# sch_ma_carte_alim_v1_1.net
KiCad netlist of a schematic drawn in EAGLE
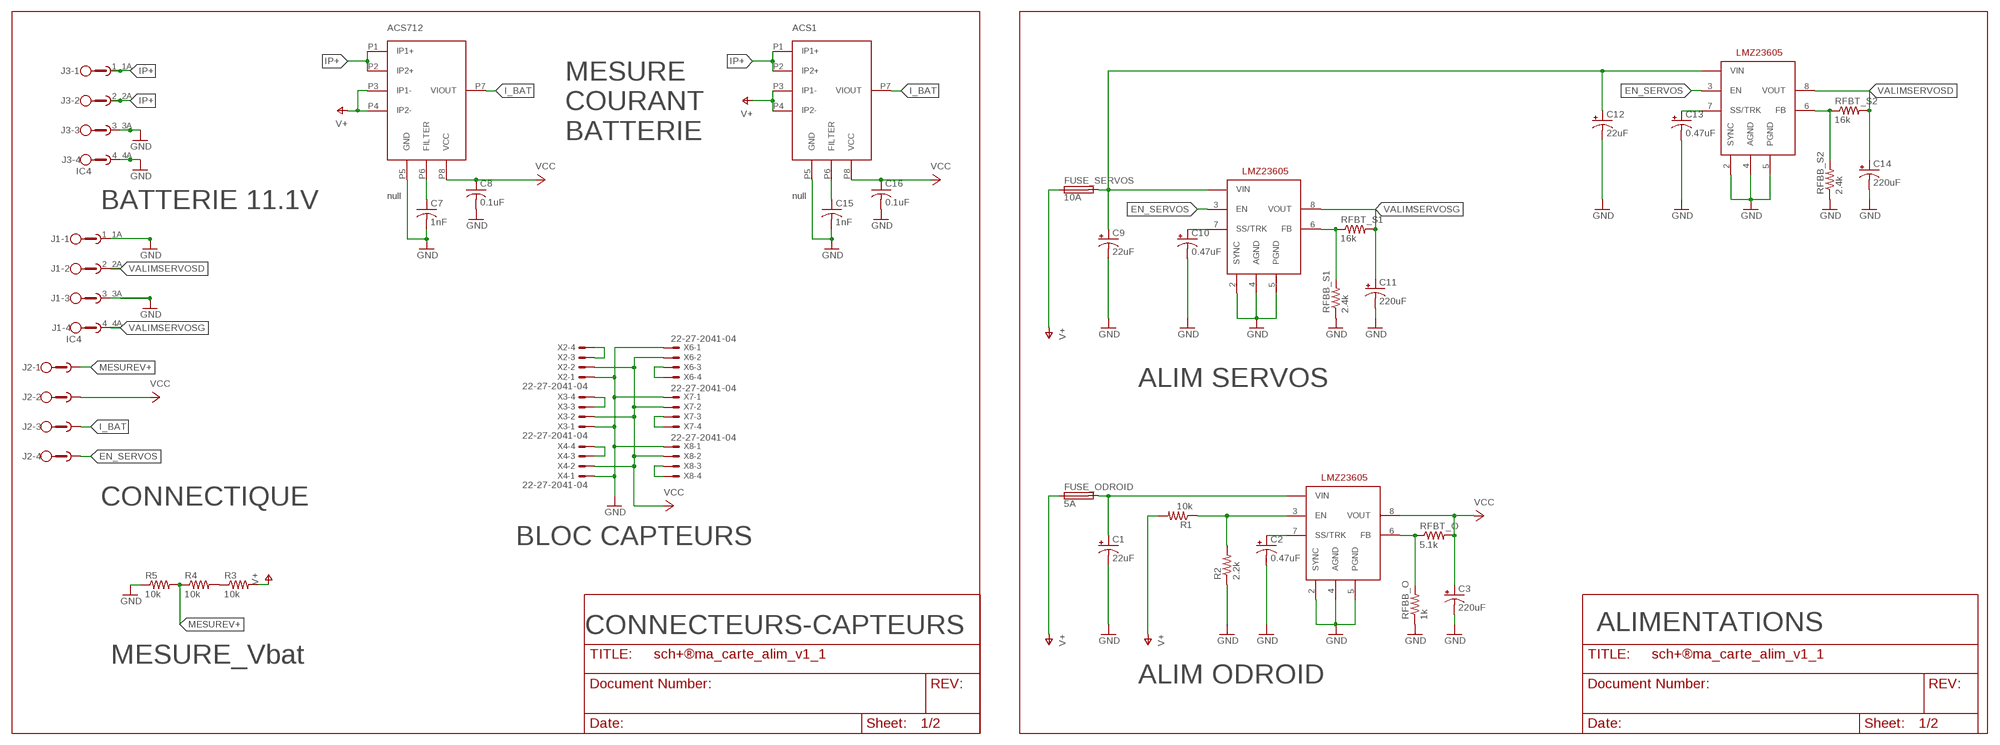
[diagram p0: schematic, sheet 1]

(export (version "E")
  (design (tool "Eeschema 10.0.6"))
  (components
    (comp (ref "ACS1")
      (value "null")
      (footprint "eagle-import:ACS712")
      (libsource (lib "eagle-import") (part "ACS712"))
    )
    (comp (ref "ACS712")
      (value "null")
      (footprint "eagle-import:ACS712")
      (libsource (lib "eagle-import") (part "ACS712"))
    )
    (comp (ref "ALIM_ODROID")
      (value "LMZ23605")
      (footprint "eagle-import:LMZ23605")
      (libsource (lib "eagle-import") (part "LMZ23605"))
    )
    (comp (ref "ALIM_SERVOS1")
      (value "LMZ23605")
      (footprint "eagle-import:LMZ23605")
      (libsource (lib "eagle-import") (part "LMZ23605"))
    )
    (comp (ref "ALIM_SERVOS2")
      (value "LMZ23605")
      (footprint "eagle-import:LMZ23605")
      (libsource (lib "eagle-import") (part "LMZ23605"))
    )
    (comp (ref "C1")
      (value "22uF")
      (footprint "eagle-import:E2,5-6")
      (libsource (lib "eagle-import") (part "CPOL-USE2.5-6"))
    )
    (comp (ref "C2")
      (value "0.47uF")
      (footprint "eagle-import:E2-5")
      (libsource (lib "eagle-import") (part "CPOL-USE2-5"))
    )
    (comp (ref "C3")
      (value "220uF")
      (footprint "eagle-import:E3,5-8")
      (libsource (lib "eagle-import") (part "CPOL-USE3.5-8"))
    )
    (comp (ref "C7")
      (value "1nF")
      (footprint "eagle-import:C0805")
      (libsource (lib "eagle-import") (part "C-USC0805"))
    )
    (comp (ref "C8")
      (value "0.1uF")
      (footprint "eagle-import:C0805")
      (libsource (lib "eagle-import") (part "C-USC0805"))
    )
    (comp (ref "C9")
      (value "22uF")
      (footprint "eagle-import:E2,5-6")
      (libsource (lib "eagle-import") (part "CPOL-USE2.5-6"))
    )
    (comp (ref "C10")
      (value "0.47uF")
      (footprint "eagle-import:E2-5")
      (libsource (lib "eagle-import") (part "CPOL-USE2-5"))
    )
    (comp (ref "C11")
      (value "220uF")
      (footprint "eagle-import:E3,5-8")
      (libsource (lib "eagle-import") (part "CPOL-USE3.5-8"))
    )
    (comp (ref "C12")
      (value "22uF")
      (footprint "eagle-import:E2,5-6")
      (libsource (lib "eagle-import") (part "CPOL-USE2.5-6"))
    )
    (comp (ref "C13")
      (value "0.47uF")
      (footprint "eagle-import:E2-5")
      (libsource (lib "eagle-import") (part "CPOL-USE2-5"))
    )
    (comp (ref "C14")
      (value "220uF")
      (footprint "eagle-import:E3,5-8")
      (libsource (lib "eagle-import") (part "CPOL-USE3.5-8"))
    )
    (comp (ref "C15")
      (value "1nF")
      (footprint "eagle-import:C0805")
      (libsource (lib "eagle-import") (part "C-USC0805"))
    )
    (comp (ref "C16")
      (value "0.1uF")
      (footprint "eagle-import:C0805")
      (libsource (lib "eagle-import") (part "C-USC0805"))
    )
    (comp (ref "FUSE_ODROID")
      (value "5A")
      (footprint "eagle-import:SH22,5")
      (fields (field (name "MF") "SCHURTER") (field (name "MPN") "0031.8201"))
      (libsource (lib "eagle-import") (part "SH22,5"))
    )
    (comp (ref "FUSE_SERVOS")
      (value "10A")
      (footprint "eagle-import:SH22,5")
      (fields (field (name "MF") "SCHURTER") (field (name "MPN") "0031.8201"))
      (libsource (lib "eagle-import") (part "SH22,5"))
    )
    (comp (ref "J1")
      (value "IC4")
      (footprint "eagle-import:IC4")
      (libsource (lib "eagle-import") (part "IC4"))
    )
    (comp (ref "J2")
      (value "MC1.5/4-G-3.81")
      (footprint "eagle-import:MC1.5_4-G-3.81")
      (libsource (lib "eagle-import") (part "MC1.5/4-G-3.81"))
    )
    (comp (ref "J3")
      (value "IC4")
      (footprint "eagle-import:IC4")
      (libsource (lib "eagle-import") (part "IC4"))
    )
    (comp (ref "R1")
      (value "10k")
      (footprint "eagle-import:R0805")
      (libsource (lib "eagle-import") (part "R-US_R0805"))
    )
    (comp (ref "R2")
      (value "2.2k")
      (footprint "eagle-import:R0805")
      (libsource (lib "eagle-import") (part "R-US_R0805"))
    )
    (comp (ref "R3")
      (value "10k")
      (footprint "eagle-import:M0805")
      (libsource (lib "eagle-import") (part "R-US_M0805"))
    )
    (comp (ref "R4")
      (value "10k")
      (footprint "eagle-import:M0805")
      (libsource (lib "eagle-import") (part "R-US_M0805"))
    )
    (comp (ref "R5")
      (value "10k")
      (footprint "eagle-import:M0805")
      (libsource (lib "eagle-import") (part "R-US_M0805"))
    )
    (comp (ref "RFBB_O")
      (value "1k")
      (footprint "eagle-import:R0805")
      (libsource (lib "eagle-import") (part "R-US_R0805"))
    )
    (comp (ref "RFBB_S1")
      (value "2.4k")
      (footprint "eagle-import:R0805")
      (libsource (lib "eagle-import") (part "R-US_R0805"))
    )
    (comp (ref "RFBB_S2")
      (value "2.4k")
      (footprint "eagle-import:R0805")
      (libsource (lib "eagle-import") (part "R-US_R0805"))
    )
    (comp (ref "RFBT_O")
      (value "5.1k")
      (footprint "eagle-import:R0805")
      (libsource (lib "eagle-import") (part "R-US_R0805"))
    )
    (comp (ref "RFBT_S1")
      (value "16k")
      (footprint "eagle-import:R0805")
      (libsource (lib "eagle-import") (part "R-US_R0805"))
    )
    (comp (ref "RFBT_S2")
      (value "16k")
      (footprint "eagle-import:R0805")
      (libsource (lib "eagle-import") (part "R-US_R0805"))
    )
    (comp (ref "X2")
      (value "22-27-2041-04")
      (footprint "eagle-import:6410-04")
      (libsource (lib "eagle-import") (part "22-?-0427-2041"))
    )
    (comp (ref "X3")
      (value "22-27-2041-04")
      (footprint "eagle-import:6410-04")
      (libsource (lib "eagle-import") (part "22-?-0427-2041"))
    )
    (comp (ref "X4")
      (value "22-27-2041-04")
      (footprint "eagle-import:6410-04")
      (libsource (lib "eagle-import") (part "22-?-0427-2041"))
    )
    (comp (ref "X6")
      (value "22-27-2041-04")
      (footprint "eagle-import:6410-04")
      (libsource (lib "eagle-import") (part "22-?-0427-2041"))
    )
    (comp (ref "X7")
      (value "22-27-2041-04")
      (footprint "eagle-import:6410-04")
      (libsource (lib "eagle-import") (part "22-?-0427-2041"))
    )
    (comp (ref "X8")
      (value "22-27-2041-04")
      (footprint "eagle-import:6410-04")
      (libsource (lib "eagle-import") (part "22-?-0427-2041"))
    )
  )
  (nets
    (net (code "1") (name "EN_SERVOS") (class "Default")
      (node (ref "ALIM_SERVOS1") (pin "3") (pinfunction "EN_3") (pintype "bidirectional"))
      (node (ref "ALIM_SERVOS2") (pin "3") (pinfunction "EN_3") (pintype "bidirectional"))
      (node (ref "J2") (pin "4") (pinfunction "1_4") (pintype "passive"))
    )
    (net (code "2") (name "GND") (class "Default")
      (node (ref "ACS1") (pin "P5") (pinfunction "GND_P5") (pintype "power_in"))
      (node (ref "ACS712") (pin "P5") (pinfunction "GND_P5") (pintype "power_in"))
      (node (ref "ALIM_ODROID") (pin "2") (pinfunction "SYNC_2") (pintype "bidirectional"))
      (node (ref "ALIM_ODROID") (pin "4") (pinfunction "AGND_4") (pintype "bidirectional"))
      (node (ref "ALIM_ODROID") (pin "5") (pinfunction "PGND_5") (pintype "bidirectional"))
      (node (ref "ALIM_SERVOS1") (pin "2") (pinfunction "SYNC_2") (pintype "bidirectional"))
      (node (ref "ALIM_SERVOS1") (pin "4") (pinfunction "AGND_4") (pintype "bidirectional"))
      (node (ref "ALIM_SERVOS1") (pin "5") (pinfunction "PGND_5") (pintype "bidirectional"))
      (node (ref "ALIM_SERVOS2") (pin "2") (pinfunction "SYNC_2") (pintype "bidirectional"))
      (node (ref "ALIM_SERVOS2") (pin "4") (pinfunction "AGND_4") (pintype "bidirectional"))
      (node (ref "ALIM_SERVOS2") (pin "5") (pinfunction "PGND_5") (pintype "bidirectional"))
      (node (ref "C1") (pin "-") (pinfunction "-_-") (pintype "passive"))
      (node (ref "C10") (pin "-") (pinfunction "-_-") (pintype "passive"))
      (node (ref "C11") (pin "-") (pinfunction "-_-") (pintype "passive"))
      (node (ref "C12") (pin "-") (pinfunction "-_-") (pintype "passive"))
      (node (ref "C13") (pin "-") (pinfunction "-_-") (pintype "passive"))
      (node (ref "C14") (pin "-") (pinfunction "-_-") (pintype "passive"))
      (node (ref "C15") (pin "2") (pinfunction "2_2") (pintype "passive"))
      (node (ref "C16") (pin "2") (pinfunction "2_2") (pintype "passive"))
      (node (ref "C2") (pin "-") (pinfunction "-_-") (pintype "passive"))
      (node (ref "C3") (pin "-") (pinfunction "-_-") (pintype "passive"))
      (node (ref "C7") (pin "2") (pinfunction "2_2") (pintype "passive"))
      (node (ref "C8") (pin "2") (pinfunction "2_2") (pintype "passive"))
      (node (ref "C9") (pin "-") (pinfunction "-_-") (pintype "passive"))
      (node (ref "J1") (pin "1") (pinfunction "1_1") (pintype "passive"))
      (node (ref "J1") (pin "1A") (pinfunction "2_1A") (pintype "passive"))
      (node (ref "J1") (pin "3") (pinfunction "1_3") (pintype "passive"))
      (node (ref "J1") (pin "3A") (pinfunction "2_3A") (pintype "passive"))
      (node (ref "J3") (pin "3") (pinfunction "1_3") (pintype "passive"))
      (node (ref "J3") (pin "3A") (pinfunction "2_3A") (pintype "passive"))
      (node (ref "J3") (pin "4") (pinfunction "1_4") (pintype "passive"))
      (node (ref "J3") (pin "4A") (pinfunction "2_4A") (pintype "passive"))
      (node (ref "R2") (pin "1") (pinfunction "1_1") (pintype "passive"))
      (node (ref "R5") (pin "1") (pinfunction "1_1") (pintype "passive"))
      (node (ref "RFBB_O") (pin "1") (pinfunction "1_1") (pintype "passive"))
      (node (ref "RFBB_S1") (pin "1") (pinfunction "1_1") (pintype "passive"))
      (node (ref "RFBB_S2") (pin "1") (pinfunction "1_1") (pintype "passive"))
      (node (ref "X2") (pin "1") (pinfunction "S_1") (pintype "passive"))
      (node (ref "X3") (pin "1") (pinfunction "S_1") (pintype "passive"))
      (node (ref "X4") (pin "1") (pinfunction "S_1") (pintype "passive"))
      (node (ref "X6") (pin "1") (pinfunction "S_1") (pintype "passive"))
      (node (ref "X7") (pin "1") (pinfunction "S_1") (pintype "passive"))
      (node (ref "X8") (pin "1") (pinfunction "S_1") (pintype "passive"))
    )
    (net (code "3") (name "IP+") (class "Default")
      (node (ref "ACS1") (pin "P1") (pinfunction "IP1+_P1") (pintype "input"))
      (node (ref "ACS1") (pin "P2") (pinfunction "IP2+_P2") (pintype "input"))
      (node (ref "ACS712") (pin "P1") (pinfunction "IP1+_P1") (pintype "input"))
      (node (ref "ACS712") (pin "P2") (pinfunction "IP2+_P2") (pintype "input"))
      (node (ref "J3") (pin "1") (pinfunction "1_1") (pintype "passive"))
      (node (ref "J3") (pin "1A") (pinfunction "2_1A") (pintype "passive"))
      (node (ref "J3") (pin "2") (pinfunction "1_2") (pintype "passive"))
      (node (ref "J3") (pin "2A") (pinfunction "2_2A") (pintype "passive"))
    )
    (net (code "4") (name "I_BAT") (class "Default")
      (node (ref "ACS1") (pin "P7") (pinfunction "VIOUT_P7") (pintype "output"))
      (node (ref "ACS712") (pin "P7") (pinfunction "VIOUT_P7") (pintype "output"))
      (node (ref "J2") (pin "3") (pinfunction "1_3") (pintype "passive"))
    )
    (net (code "5") (name "MESUREV+") (class "Default")
      (node (ref "J2") (pin "1") (pinfunction "1_1") (pintype "passive"))
      (node (ref "R4") (pin "1") (pinfunction "1_1") (pintype "passive"))
      (node (ref "R5") (pin "2") (pinfunction "2_2") (pintype "passive"))
    )
    (net (code "6") (name "Net-(ACS1-FILTER)") (class "Default")
      (node (ref "ACS1") (pin "P6") (pinfunction "FILTER_P6") (pintype "bidirectional"))
      (node (ref "C15") (pin "1") (pinfunction "1_1") (pintype "passive"))
    )
    (net (code "7") (name "Net-(ACS712-FILTER)") (class "Default")
      (node (ref "ACS712") (pin "P6") (pinfunction "FILTER_P6") (pintype "bidirectional"))
      (node (ref "C7") (pin "1") (pinfunction "1_1") (pintype "passive"))
    )
    (net (code "8") (name "Net-(ALIM_ODROID-EN)") (class "Default")
      (node (ref "ALIM_ODROID") (pin "3") (pinfunction "EN_3") (pintype "bidirectional"))
      (node (ref "R1") (pin "1") (pinfunction "1_1") (pintype "passive"))
      (node (ref "R2") (pin "2") (pinfunction "2_2") (pintype "passive"))
    )
    (net (code "9") (name "Net-(ALIM_ODROID-FB)") (class "Default")
      (node (ref "ALIM_ODROID") (pin "6") (pinfunction "FB_6") (pintype "bidirectional"))
      (node (ref "RFBB_O") (pin "2") (pinfunction "2_2") (pintype "passive"))
      (node (ref "RFBT_O") (pin "1") (pinfunction "1_1") (pintype "passive"))
    )
    (net (code "10") (name "Net-(ALIM_ODROID-SS{slash}TRK)") (class "Default")
      (node (ref "ALIM_ODROID") (pin "7") (pinfunction "SS/TRK_7") (pintype "bidirectional"))
      (node (ref "C2") (pin "+") (pinfunction "+_+") (pintype "passive"))
    )
    (net (code "11") (name "Net-(ALIM_ODROID-VIN)") (class "Default")
      (node (ref "ALIM_ODROID") (pin "1") (pinfunction "VIN_1") (pintype "bidirectional"))
      (node (ref "C1") (pin "+") (pinfunction "+_+") (pintype "passive"))
      (node (ref "FUSE_ODROID") (pin "2") (pinfunction "2_2") (pintype "passive"))
    )
    (net (code "12") (name "Net-(ALIM_SERVOS1-FB)") (class "Default")
      (node (ref "ALIM_SERVOS1") (pin "6") (pinfunction "FB_6") (pintype "bidirectional"))
      (node (ref "RFBB_S1") (pin "2") (pinfunction "2_2") (pintype "passive"))
      (node (ref "RFBT_S1") (pin "1") (pinfunction "1_1") (pintype "passive"))
    )
    (net (code "13") (name "Net-(ALIM_SERVOS1-SS{slash}TRK)") (class "Default")
      (node (ref "ALIM_SERVOS1") (pin "7") (pinfunction "SS/TRK_7") (pintype "bidirectional"))
      (node (ref "C10") (pin "+") (pinfunction "+_+") (pintype "passive"))
    )
    (net (code "14") (name "Net-(ALIM_SERVOS1-VIN)") (class "Default")
      (node (ref "ALIM_SERVOS1") (pin "1") (pinfunction "VIN_1") (pintype "bidirectional"))
      (node (ref "ALIM_SERVOS2") (pin "1") (pinfunction "VIN_1") (pintype "bidirectional"))
      (node (ref "C12") (pin "+") (pinfunction "+_+") (pintype "passive"))
      (node (ref "C9") (pin "+") (pinfunction "+_+") (pintype "passive"))
      (node (ref "FUSE_SERVOS") (pin "2") (pinfunction "2_2") (pintype "passive"))
    )
    (net (code "15") (name "Net-(ALIM_SERVOS2-FB)") (class "Default")
      (node (ref "ALIM_SERVOS2") (pin "6") (pinfunction "FB_6") (pintype "bidirectional"))
      (node (ref "RFBB_S2") (pin "2") (pinfunction "2_2") (pintype "passive"))
      (node (ref "RFBT_S2") (pin "1") (pinfunction "1_1") (pintype "passive"))
    )
    (net (code "16") (name "Net-(ALIM_SERVOS2-SS{slash}TRK)") (class "Default")
      (node (ref "ALIM_SERVOS2") (pin "7") (pinfunction "SS/TRK_7") (pintype "bidirectional"))
      (node (ref "C13") (pin "+") (pinfunction "+_+") (pintype "passive"))
    )
    (net (code "17") (name "Net-(R3-Pad1)") (class "Default")
      (node (ref "R3") (pin "1") (pinfunction "1_1") (pintype "passive"))
      (node (ref "R4") (pin "2") (pinfunction "2_2") (pintype "passive"))
    )
    (net (code "18") (name "Net-(X2C-S)") (class "Default")
      (node (ref "X2") (pin "3") (pinfunction "S_3") (pintype "passive"))
      (node (ref "X2") (pin "4") (pinfunction "S_4") (pintype "passive"))
    )
    (net (code "19") (name "Net-(X3C-S)") (class "Default")
      (node (ref "X3") (pin "3") (pinfunction "S_3") (pintype "passive"))
      (node (ref "X3") (pin "4") (pinfunction "S_4") (pintype "passive"))
    )
    (net (code "20") (name "Net-(X4C-S)") (class "Default")
      (node (ref "X4") (pin "3") (pinfunction "S_3") (pintype "passive"))
      (node (ref "X4") (pin "4") (pinfunction "S_4") (pintype "passive"))
    )
    (net (code "21") (name "Net-(X6C-S)") (class "Default")
      (node (ref "X6") (pin "3") (pinfunction "S_3") (pintype "passive"))
      (node (ref "X6") (pin "4") (pinfunction "S_4") (pintype "passive"))
    )
    (net (code "22") (name "Net-(X7C-S)") (class "Default")
      (node (ref "X7") (pin "3") (pinfunction "S_3") (pintype "passive"))
      (node (ref "X7") (pin "4") (pinfunction "S_4") (pintype "passive"))
    )
    (net (code "23") (name "Net-(X8C-S)") (class "Default")
      (node (ref "X8") (pin "3") (pinfunction "S_3") (pintype "passive"))
      (node (ref "X8") (pin "4") (pinfunction "S_4") (pintype "passive"))
    )
    (net (code "24") (name "V+") (class "Default")
      (node (ref "ACS1") (pin "P3") (pinfunction "IP1-_P3") (pintype "input"))
      (node (ref "ACS1") (pin "P4") (pinfunction "IP2-_P4") (pintype "input"))
      (node (ref "ACS712") (pin "P3") (pinfunction "IP1-_P3") (pintype "input"))
      (node (ref "ACS712") (pin "P4") (pinfunction "IP2-_P4") (pintype "input"))
      (node (ref "FUSE_ODROID") (pin "1") (pinfunction "1_1") (pintype "passive"))
      (node (ref "FUSE_SERVOS") (pin "1") (pinfunction "1_1") (pintype "passive"))
      (node (ref "R1") (pin "2") (pinfunction "2_2") (pintype "passive"))
      (node (ref "R3") (pin "2") (pinfunction "2_2") (pintype "passive"))
    )
    (net (code "25") (name "VALIMSERVOSD") (class "Default")
      (node (ref "ALIM_SERVOS2") (pin "8") (pinfunction "VOUT_8") (pintype "bidirectional"))
      (node (ref "C14") (pin "+") (pinfunction "+_+") (pintype "passive"))
      (node (ref "J1") (pin "2") (pinfunction "1_2") (pintype "passive"))
      (node (ref "J1") (pin "2A") (pinfunction "2_2A") (pintype "passive"))
      (node (ref "RFBT_S2") (pin "2") (pinfunction "2_2") (pintype "passive"))
    )
    (net (code "26") (name "VALIMSERVOSG") (class "Default")
      (node (ref "ALIM_SERVOS1") (pin "8") (pinfunction "VOUT_8") (pintype "bidirectional"))
      (node (ref "C11") (pin "+") (pinfunction "+_+") (pintype "passive"))
      (node (ref "J1") (pin "4") (pinfunction "1_4") (pintype "passive"))
      (node (ref "J1") (pin "4A") (pinfunction "2_4A") (pintype "passive"))
      (node (ref "RFBT_S1") (pin "2") (pinfunction "2_2") (pintype "passive"))
    )
    (net (code "27") (name "VCC") (class "Default")
      (node (ref "ACS1") (pin "P8") (pinfunction "VCC_P8") (pintype "power_in"))
      (node (ref "ACS712") (pin "P8") (pinfunction "VCC_P8") (pintype "power_in"))
      (node (ref "ALIM_ODROID") (pin "8") (pinfunction "VOUT_8") (pintype "bidirectional"))
      (node (ref "C16") (pin "1") (pinfunction "1_1") (pintype "passive"))
      (node (ref "C3") (pin "+") (pinfunction "+_+") (pintype "passive"))
      (node (ref "C8") (pin "1") (pinfunction "1_1") (pintype "passive"))
      (node (ref "J2") (pin "2") (pinfunction "1_2") (pintype "passive"))
      (node (ref "RFBT_O") (pin "2") (pinfunction "2_2") (pintype "passive"))
      (node (ref "X2") (pin "2") (pinfunction "S_2") (pintype "passive"))
      (node (ref "X3") (pin "2") (pinfunction "S_2") (pintype "passive"))
      (node (ref "X4") (pin "2") (pinfunction "S_2") (pintype "passive"))
      (node (ref "X6") (pin "2") (pinfunction "S_2") (pintype "passive"))
      (node (ref "X7") (pin "2") (pinfunction "S_2") (pintype "passive"))
      (node (ref "X8") (pin "2") (pinfunction "S_2") (pintype "passive"))
    )
  )
)
